# heater_control.net
KiCad netlist of a schematic drawn in Altium Designer
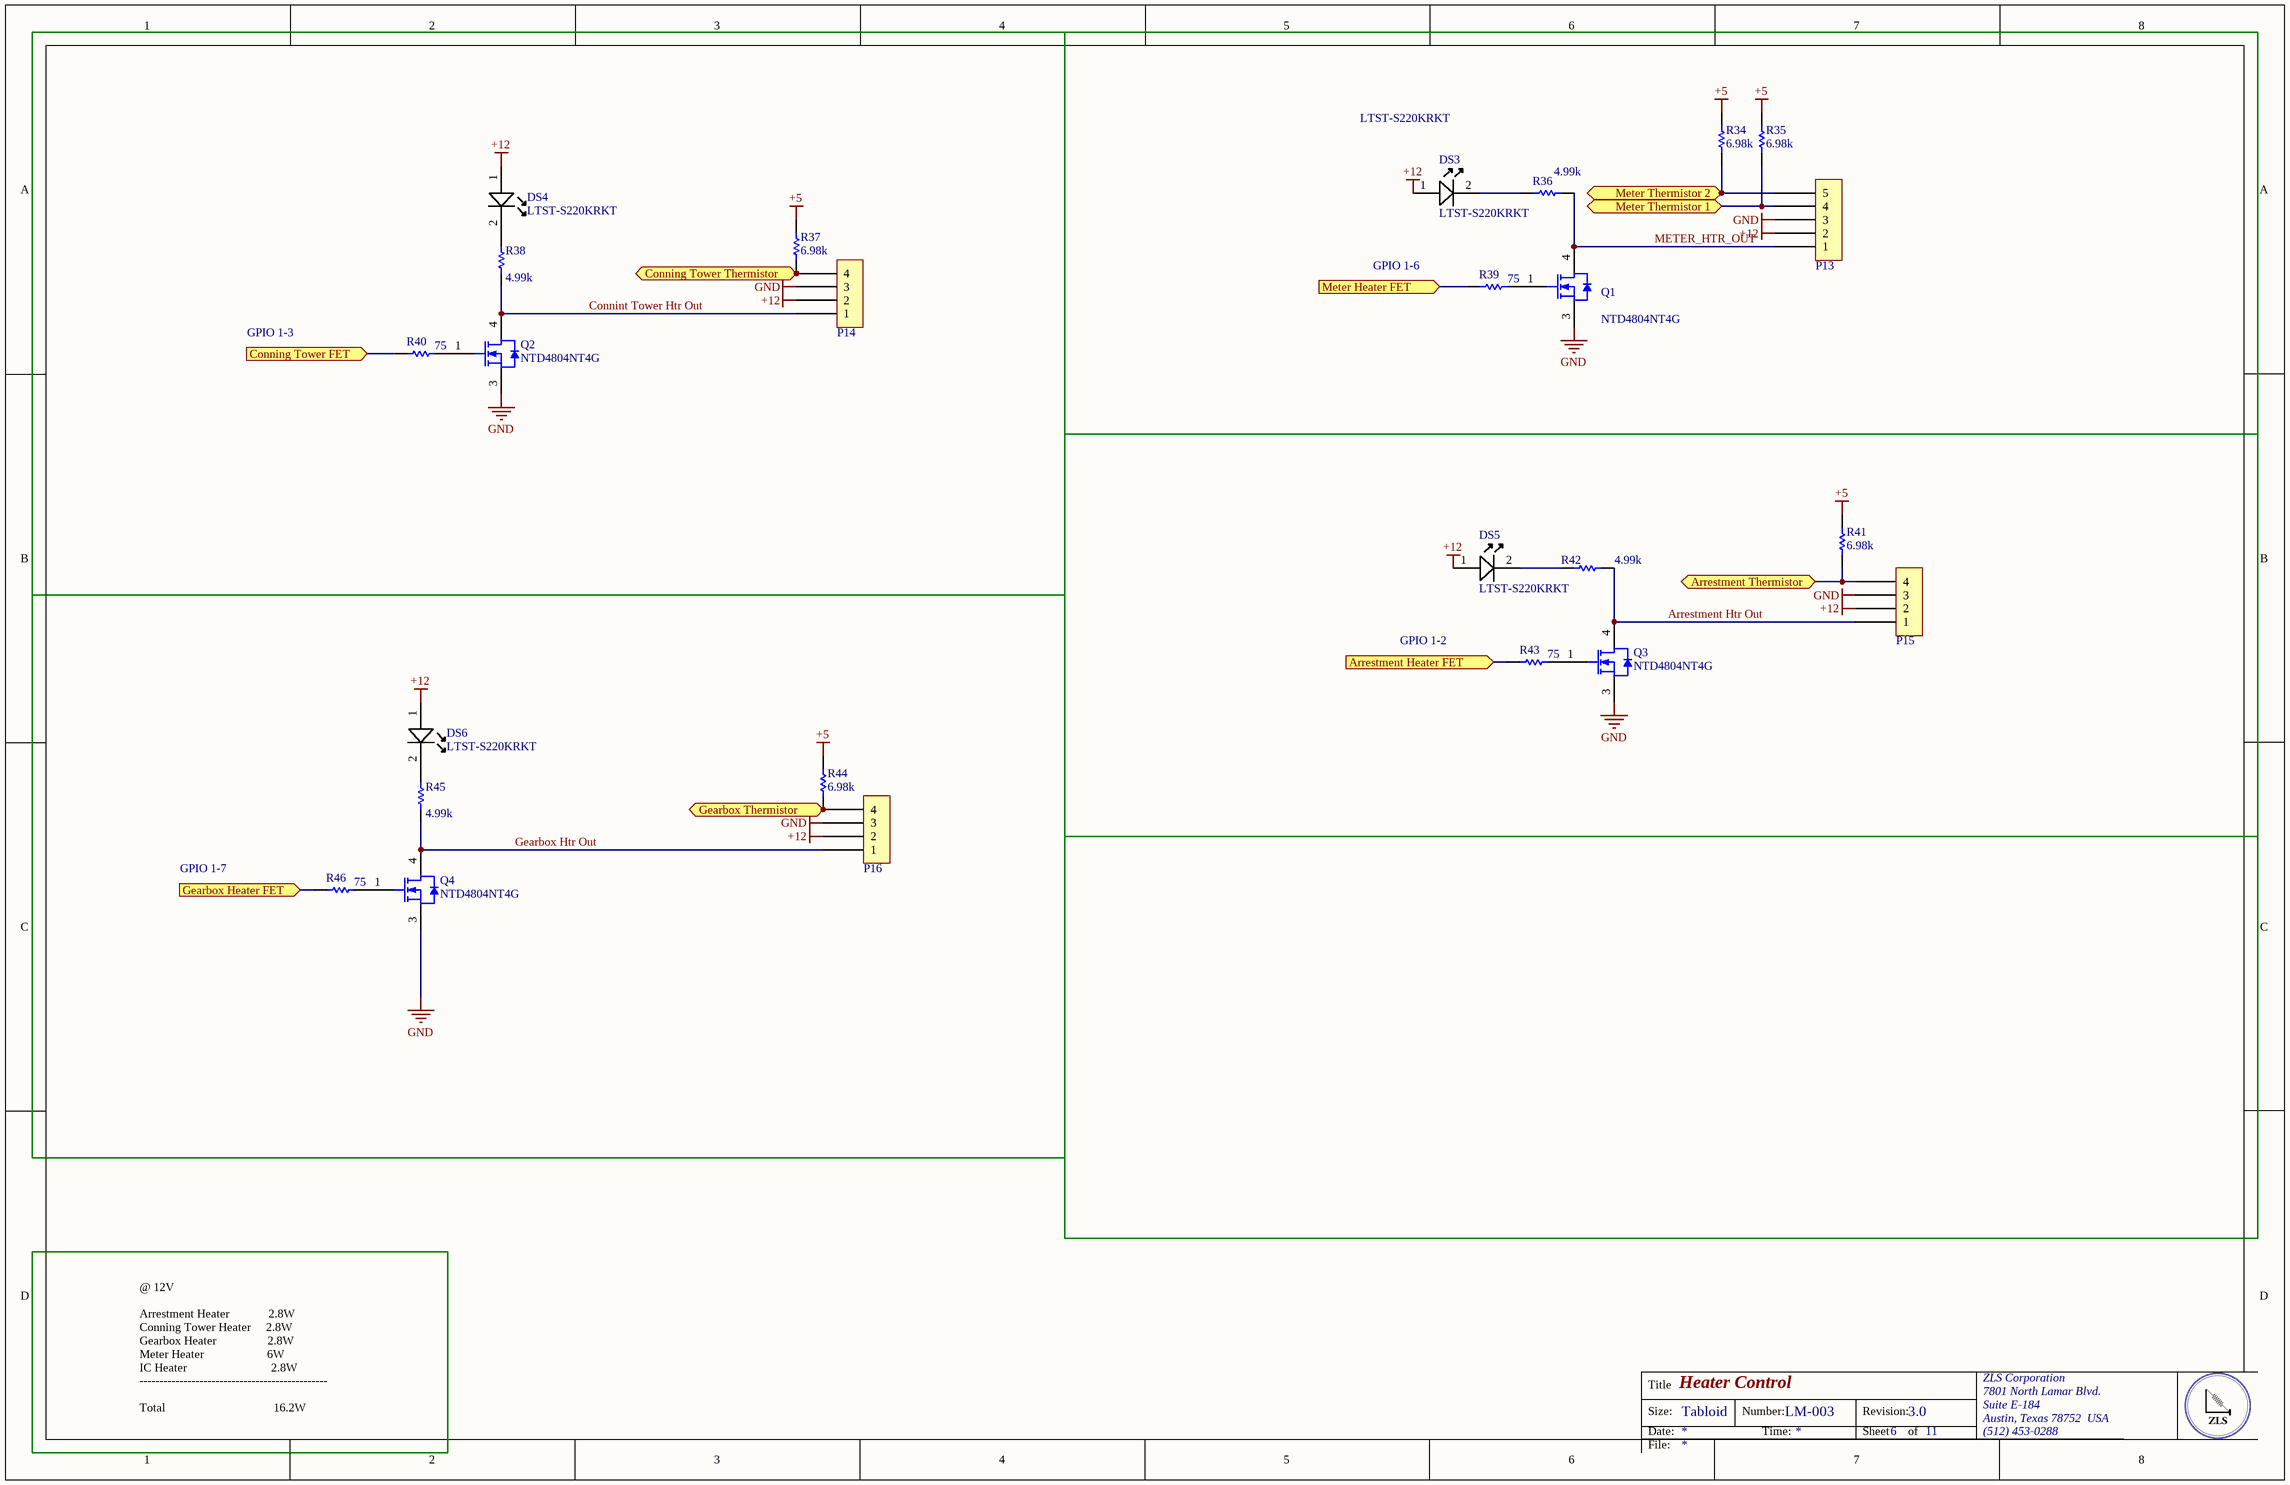
[diagram p0: heater_control.SchDoc]

(export (version "E")
  (design (tool "Eeschema 10.0.6"))
  (components
    (comp (ref "DS3")
      (value "Visible Name Value Type    False Description Lite-On LTST-S220KRKT Red LED, 631 nm 2012 (0805) Side View, Rectangle Lens SMD package STRING")
      (footprint "0805C_L")
      (fields
        (field (name "MANUFACTURER") "Vishay / Lite-On")
        (field (name "MANUFACTURER PART NUMBER") "LTST-S220KRKT")
      )
      (libsource (lib "*") (part "LED A/K"))
    )
    (comp (ref "DS4")
      (value "Visible Name Value Type    False Description Lite-On LTST-S220KRKT Red LED, 631 nm 2012 (0805) Side View, Rectangle Lens SMD package STRING")
      (footprint "0805C_L")
      (fields
        (field (name "MANUFACTURER") "Vishay / Lite-On")
        (field (name "MANUFACTURER PART NUMBER") "LTST-S220KRKT")
      )
      (libsource (lib "*") (part "LED A/K"))
    )
    (comp (ref "DS5")
      (value "Visible Name Value Type    False Description Lite-On LTST-S220KRKT Red LED, 631 nm 2012 (0805) Side View, Rectangle Lens SMD package STRING")
      (footprint "0805C_L")
      (fields
        (field (name "MANUFACTURER") "Vishay / Lite-On")
        (field (name "MANUFACTURER PART NUMBER") "LTST-S220KRKT")
      )
      (libsource (lib "*") (part "LED A/K"))
    )
    (comp (ref "DS6")
      (value "Visible Name Value Type    False Description Lite-On LTST-S220KRKT Red LED, 631 nm 2012 (0805) Side View, Rectangle Lens SMD package STRING")
      (footprint "0805C_L")
      (fields
        (field (name "MANUFACTURER") "Vishay / Lite-On")
        (field (name "MANUFACTURER PART NUMBER") "LTST-S220KRKT")
      )
      (libsource (lib "*") (part "LED A/K"))
    )
    (comp (ref "P13")
      (value "IPL1-105-02-F-S-K")
      (footprint "IPL1-105-02-F-S-K")
      (libsource (lib "ZLS_Schematic_lib") (part "IPL1-105-02-F-S"))
    )
    (comp (ref "P14")
      (value "IPL1-104-02-F-S-K")
      (footprint "IPL1-104-02-F-S-K")
      (libsource (lib "ZLS_Schematic_lib") (part "IPL1-104-02-F-S"))
    )
    (comp (ref "P15")
      (value "IPL1-104-02-F-S-K")
      (footprint "IPL1-104-02-F-S-K")
      (libsource (lib "ZLS_Schematic_lib") (part "IPL1-104-02-F-S"))
    )
    (comp (ref "P16")
      (value "IPL1-104-02-F-S-K")
      (footprint "IPL1-104-02-F-S-K")
      (libsource (lib "ZLS_Schematic_lib") (part "IPL1-104-02-F-S"))
    )
    (comp (ref "Q1")
      (value "NTD4804NT4G")
      (footprint "ONSC-DPAK-3-369AA-01_V")
      (description "Power MOSFET, 30 V, 117 A, Single N-Channel, 3-Pin DPAK, Pb-Free, Tape and Reel")
      (fields (field (name "MANUFACTURER") "On Semiconductor"))
      (libsource (lib "Altium Content Vault") (part "CMP-1058-00341-1"))
    )
    (comp (ref "Q2")
      (value "NTD4804NT4G")
      (footprint "ONSC-DPAK-3-369AA-01_V")
      (description "Power MOSFET, 30 V, 117 A, Single N-Channel, 3-Pin DPAK, Pb-Free, Tape and Reel")
      (fields (field (name "MANUFACTURER") "On Semiconductor"))
      (libsource (lib "Altium Content Vault") (part "CMP-1058-00341-1"))
    )
    (comp (ref "Q3")
      (value "NTD4804NT4G")
      (footprint "ONSC-DPAK-3-369AA-01_V")
      (description "Power MOSFET, 30 V, 117 A, Single N-Channel, 3-Pin DPAK, Pb-Free, Tape and Reel")
      (fields (field (name "MANUFACTURER") "On Semiconductor"))
      (libsource (lib "Altium Content Vault") (part "CMP-1058-00341-1"))
    )
    (comp (ref "Q4")
      (value "NTD4804NT4G")
      (footprint "ONSC-DPAK-3-369AA-01_V")
      (description "Power MOSFET, 30 V, 117 A, Single N-Channel, 3-Pin DPAK, Pb-Free, Tape and Reel")
      (fields (field (name "MANUFACTURER") "On Semiconductor"))
      (libsource (lib "Altium Content Vault") (part "CMP-1058-00341-1"))
    )
    (comp (ref "R34")
      (value "6K98 1% 0805(2012)")
      (footprint "RESC0805(2012)_N")
      (description "6K98 0.125W 1% 0805 (2012 Metric)  SMD")
      (fields
        (field (name "MANUFACTURER") "Vishay Dale")
        (field (name "MANUFACTURER PART NUMBER") "CRCW08056K98FKEA")
        (field (name "RESISTANCE (OHMS)") "6.98k")
      )
      (libsource (lib "Altium Content Vault") (part "CMP-1013-00606-1"))
    )
    (comp (ref "R35")
      (value "6K98 1% 0805(2012)")
      (footprint "RESC0805(2012)_N")
      (description "6K98 0.125W 1% 0805 (2012 Metric)  SMD")
      (fields
        (field (name "MANUFACTURER") "Vishay Dale")
        (field (name "MANUFACTURER PART NUMBER") "CRCW08056K98FKEA")
        (field (name "RESISTANCE (OHMS)") "6.98k")
      )
      (libsource (lib "Altium Content Vault") (part "CMP-1013-00606-1"))
    )
    (comp (ref "R36")
      (value "~")
      (footprint "RESC0805(2012)_L")
      (fields
        (field (name "MANUFACTURER") "Vishay Dale")
        (field (name "MANUFACTURER PART NUMBER") "CRCW08054K99FKEA")
        (field (name "RESISTANCE (OHMS)") "4.99k")
        (field (name "TOLERANCE") "±1%")
      )
      (libsource (lib "Altium Content Vault") (part "CMP-1013-00393-1"))
    )
    (comp (ref "R37")
      (value "6K98 1% 0805(2012)")
      (footprint "RESC0805(2012)_N")
      (description "6K98 0.125W 1% 0805 (2012 Metric)  SMD")
      (fields
        (field (name "MANUFACTURER") "Vishay Dale")
        (field (name "MANUFACTURER PART NUMBER") "CRCW08056K98FKEA")
        (field (name "RESISTANCE (OHMS)") "6.98k")
      )
      (libsource (lib "Altium Content Vault") (part "CMP-1013-00606-1"))
    )
    (comp (ref "R38")
      (value "~")
      (footprint "RESC0805(2012)_L")
      (fields
        (field (name "MANUFACTURER") "Vishay Dale")
        (field (name "MANUFACTURER PART NUMBER") "CRCW08054K99FKEA")
        (field (name "RESISTANCE (OHMS)") "4.99k")
        (field (name "TOLERANCE") "±1%")
      )
      (libsource (lib "Altium Content Vault") (part "CMP-1013-00393-1"))
    )
    (comp (ref "R39")
      (value "~")
      (footprint "RESC0805(2012)_L")
      (fields
        (field (name "MANUFACTURER") "Vishay Dale")
        (field (name "MANUFACTURER PART NUMBER") "CRCW080575R0FKEA")
        (field (name "RESISTANCE (OHMS)") "75")
        (field (name "TOLERANCE") "±1%")
      )
      (libsource (lib "Altium Content Vault") (part "CMP-1013-00393-1"))
    )
    (comp (ref "R40")
      (value "~")
      (footprint "RESC0805(2012)_L")
      (fields
        (field (name "MANUFACTURER") "Vishay Dale")
        (field (name "MANUFACTURER PART NUMBER") "CRCW080575R0FKEA")
        (field (name "RESISTANCE (OHMS)") "75")
        (field (name "TOLERANCE") "±1%")
      )
      (libsource (lib "Altium Content Vault") (part "CMP-1013-00393-1"))
    )
    (comp (ref "R41")
      (value "6K98 1% 0805(2012)")
      (footprint "RESC0805(2012)_N")
      (description "6K98 0.125W 1% 0805 (2012 Metric)  SMD")
      (fields
        (field (name "MANUFACTURER") "Vishay Dale")
        (field (name "MANUFACTURER PART NUMBER") "CRCW08056K98FKEA")
        (field (name "RESISTANCE (OHMS)") "6.98k")
      )
      (libsource (lib "Altium Content Vault") (part "CMP-1013-00606-1"))
    )
    (comp (ref "R42")
      (value "~")
      (footprint "RESC0805(2012)_L")
      (fields
        (field (name "MANUFACTURER") "Vishay Dale")
        (field (name "MANUFACTURER PART NUMBER") "CRCW08054K99FKEA")
        (field (name "RESISTANCE (OHMS)") "4.99k")
        (field (name "TOLERANCE") "±1%")
      )
      (libsource (lib "Altium Content Vault") (part "CMP-1013-00393-1"))
    )
    (comp (ref "R43")
      (value "~")
      (footprint "RESC0805(2012)_L")
      (fields
        (field (name "MANUFACTURER") "Vishay Dale")
        (field (name "MANUFACTURER PART NUMBER") "CRCW080575R0FKEA")
        (field (name "RESISTANCE (OHMS)") "75")
        (field (name "TOLERANCE") "±1%")
      )
      (libsource (lib "Altium Content Vault") (part "CMP-1013-00393-1"))
    )
    (comp (ref "R44")
      (value "6K98 1% 0805(2012)")
      (footprint "RESC0805(2012)_N")
      (description "6K98 0.125W 1% 0805 (2012 Metric)  SMD")
      (fields
        (field (name "MANUFACTURER") "Vishay Dale")
        (field (name "MANUFACTURER PART NUMBER") "CRCW08056K98FKEA")
        (field (name "RESISTANCE (OHMS)") "6.98k")
      )
      (libsource (lib "Altium Content Vault") (part "CMP-1013-00606-1"))
    )
    (comp (ref "R45")
      (value "~")
      (footprint "RESC0805(2012)_L")
      (fields
        (field (name "MANUFACTURER") "Vishay Dale")
        (field (name "MANUFACTURER PART NUMBER") "CRCW08054K99FKEA")
        (field (name "RESISTANCE (OHMS)") "4.99k")
        (field (name "TOLERANCE") "±1%")
      )
      (libsource (lib "Altium Content Vault") (part "CMP-1013-00393-1"))
    )
    (comp (ref "R46")
      (value "~")
      (footprint "RESC0805(2012)_L")
      (fields
        (field (name "MANUFACTURER") "Vishay Dale")
        (field (name "MANUFACTURER PART NUMBER") "CRCW080575R0FKEA")
        (field (name "RESISTANCE (OHMS)") "75")
        (field (name "TOLERANCE") "±1%")
      )
      (libsource (lib "Altium Content Vault") (part "CMP-1013-00393-1"))
    )
  )
  (nets
    (net (code "1") (name "+5") (class "Default")
      (node (ref "R34") (pin "1") (pinfunction "1_1") (pintype "passive"))
      (node (ref "R35") (pin "2") (pinfunction "2_2") (pintype "passive"))
      (node (ref "R37") (pin "2") (pinfunction "2_2") (pintype "passive"))
      (node (ref "R41") (pin "1") (pinfunction "1_1") (pintype "passive"))
      (node (ref "R44") (pin "2") (pinfunction "2_2") (pintype "passive"))
    )
    (net (code "2") (name "+12") (class "Default")
      (node (ref "DS3") (pin "1") (pinfunction "A_1") (pintype "passive"))
      (node (ref "DS4") (pin "1") (pinfunction "A_1") (pintype "passive"))
      (node (ref "DS5") (pin "1") (pinfunction "A_1") (pintype "passive"))
      (node (ref "DS6") (pin "1") (pinfunction "A_1") (pintype "passive"))
      (node (ref "P13") (pin "2") (pinfunction "2_2") (pintype "passive"))
      (node (ref "P14") (pin "2") (pinfunction "2_2") (pintype "passive"))
      (node (ref "P15") (pin "2") (pinfunction "2_2") (pintype "passive"))
      (node (ref "P16") (pin "2") (pinfunction "2_2") (pintype "passive"))
    )
    (net (code "3") (name "/Arrestment Heater FET") (class "Default")
      (node (ref "R43") (pin "1") (pinfunction "1_1") (pintype "passive"))
    )
    (net (code "4") (name "/Arrestment Htr Out") (class "Default")
      (node (ref "P15") (pin "1") (pinfunction "1_1") (pintype "passive"))
      (node (ref "Q3") (pin "4") (pinfunction "D_4") (pintype "passive"))
      (node (ref "R42") (pin "2") (pinfunction "2_2") (pintype "passive"))
    )
    (net (code "5") (name "/Arrestment Thermistor") (class "Default")
      (node (ref "P15") (pin "4") (pinfunction "4_4") (pintype "passive"))
      (node (ref "R41") (pin "2") (pinfunction "2_2") (pintype "passive"))
    )
    (net (code "6") (name "/Conning Tower FET") (class "Default")
      (node (ref "R40") (pin "1") (pinfunction "1_1") (pintype "passive"))
    )
    (net (code "7") (name "/Conning Tower Thermistor") (class "Default")
      (node (ref "P14") (pin "4") (pinfunction "4_4") (pintype "passive"))
      (node (ref "R37") (pin "1") (pinfunction "1_1") (pintype "passive"))
    )
    (net (code "8") (name "/Connint Tower Htr Out") (class "Default")
      (node (ref "P14") (pin "1") (pinfunction "1_1") (pintype "passive"))
      (node (ref "Q2") (pin "4") (pinfunction "D_4") (pintype "passive"))
      (node (ref "R38") (pin "1") (pinfunction "1_1") (pintype "passive"))
    )
    (net (code "9") (name "/Gearbox Heater FET") (class "Default")
      (node (ref "R46") (pin "1") (pinfunction "1_1") (pintype "passive"))
    )
    (net (code "10") (name "/Gearbox Htr Out") (class "Default")
      (node (ref "P16") (pin "1") (pinfunction "1_1") (pintype "passive"))
      (node (ref "Q4") (pin "4") (pinfunction "D_4") (pintype "passive"))
      (node (ref "R45") (pin "1") (pinfunction "1_1") (pintype "passive"))
    )
    (net (code "11") (name "/Gearbox Thermistor") (class "Default")
      (node (ref "P16") (pin "4") (pinfunction "4_4") (pintype "passive"))
      (node (ref "R44") (pin "1") (pinfunction "1_1") (pintype "passive"))
    )
    (net (code "12") (name "/METER_HTR_OUT") (class "Default")
      (node (ref "P13") (pin "1") (pinfunction "1_1") (pintype "passive"))
      (node (ref "Q1") (pin "4") (pinfunction "D_4") (pintype "passive"))
      (node (ref "R36") (pin "2") (pinfunction "2_2") (pintype "passive"))
    )
    (net (code "13") (name "/Meter Heater FET") (class "Default")
      (node (ref "R39") (pin "1") (pinfunction "1_1") (pintype "passive"))
    )
    (net (code "14") (name "/Meter Thermistor 1") (class "Default")
      (node (ref "P13") (pin "4") (pinfunction "4_4") (pintype "passive"))
      (node (ref "R35") (pin "1") (pinfunction "1_1") (pintype "passive"))
    )
    (net (code "15") (name "/Meter Thermistor 2") (class "Default")
      (node (ref "P13") (pin "5") (pinfunction "5_5") (pintype "passive"))
      (node (ref "R34") (pin "2") (pinfunction "2_2") (pintype "passive"))
    )
    (net (code "16") (name "GND") (class "Default")
      (node (ref "P13") (pin "3") (pinfunction "3_3") (pintype "passive"))
      (node (ref "P14") (pin "3") (pinfunction "3_3") (pintype "passive"))
      (node (ref "P15") (pin "3") (pinfunction "3_3") (pintype "passive"))
      (node (ref "P16") (pin "3") (pinfunction "3_3") (pintype "passive"))
      (node (ref "Q1") (pin "3") (pinfunction "S_3") (pintype "passive"))
      (node (ref "Q2") (pin "3") (pinfunction "S_3") (pintype "passive"))
      (node (ref "Q3") (pin "3") (pinfunction "S_3") (pintype "passive"))
      (node (ref "Q4") (pin "3") (pinfunction "S_3") (pintype "passive"))
    )
    (net (code "17") (name "Net-(DS3-K)") (class "Default")
      (node (ref "DS3") (pin "2") (pinfunction "K_2") (pintype "passive"))
      (node (ref "R36") (pin "1") (pinfunction "1_1") (pintype "passive"))
    )
    (net (code "18") (name "Net-(DS4-K)") (class "Default")
      (node (ref "DS4") (pin "2") (pinfunction "K_2") (pintype "passive"))
      (node (ref "R38") (pin "2") (pinfunction "2_2") (pintype "passive"))
    )
    (net (code "19") (name "Net-(DS5-K)") (class "Default")
      (node (ref "DS5") (pin "2") (pinfunction "K_2") (pintype "passive"))
      (node (ref "R42") (pin "1") (pinfunction "1_1") (pintype "passive"))
    )
    (net (code "20") (name "Net-(DS6-K)") (class "Default")
      (node (ref "DS6") (pin "2") (pinfunction "K_2") (pintype "passive"))
      (node (ref "R45") (pin "2") (pinfunction "2_2") (pintype "passive"))
    )
    (net (code "21") (name "Net-(Q1-G)") (class "Default")
      (node (ref "Q1") (pin "1") (pinfunction "G_1") (pintype "passive"))
      (node (ref "R39") (pin "2") (pinfunction "2_2") (pintype "passive"))
    )
    (net (code "22") (name "Net-(Q2-G)") (class "Default")
      (node (ref "Q2") (pin "1") (pinfunction "G_1") (pintype "passive"))
      (node (ref "R40") (pin "2") (pinfunction "2_2") (pintype "passive"))
    )
    (net (code "23") (name "Net-(Q3-G)") (class "Default")
      (node (ref "Q3") (pin "1") (pinfunction "G_1") (pintype "passive"))
      (node (ref "R43") (pin "2") (pinfunction "2_2") (pintype "passive"))
    )
    (net (code "24") (name "Net-(Q4-G)") (class "Default")
      (node (ref "Q4") (pin "1") (pinfunction "G_1") (pintype "passive"))
      (node (ref "R46") (pin "2") (pinfunction "2_2") (pintype "passive"))
    )
  )
)
